# Half_Bridges.net
KiCad netlist of a schematic drawn in Altium Designer
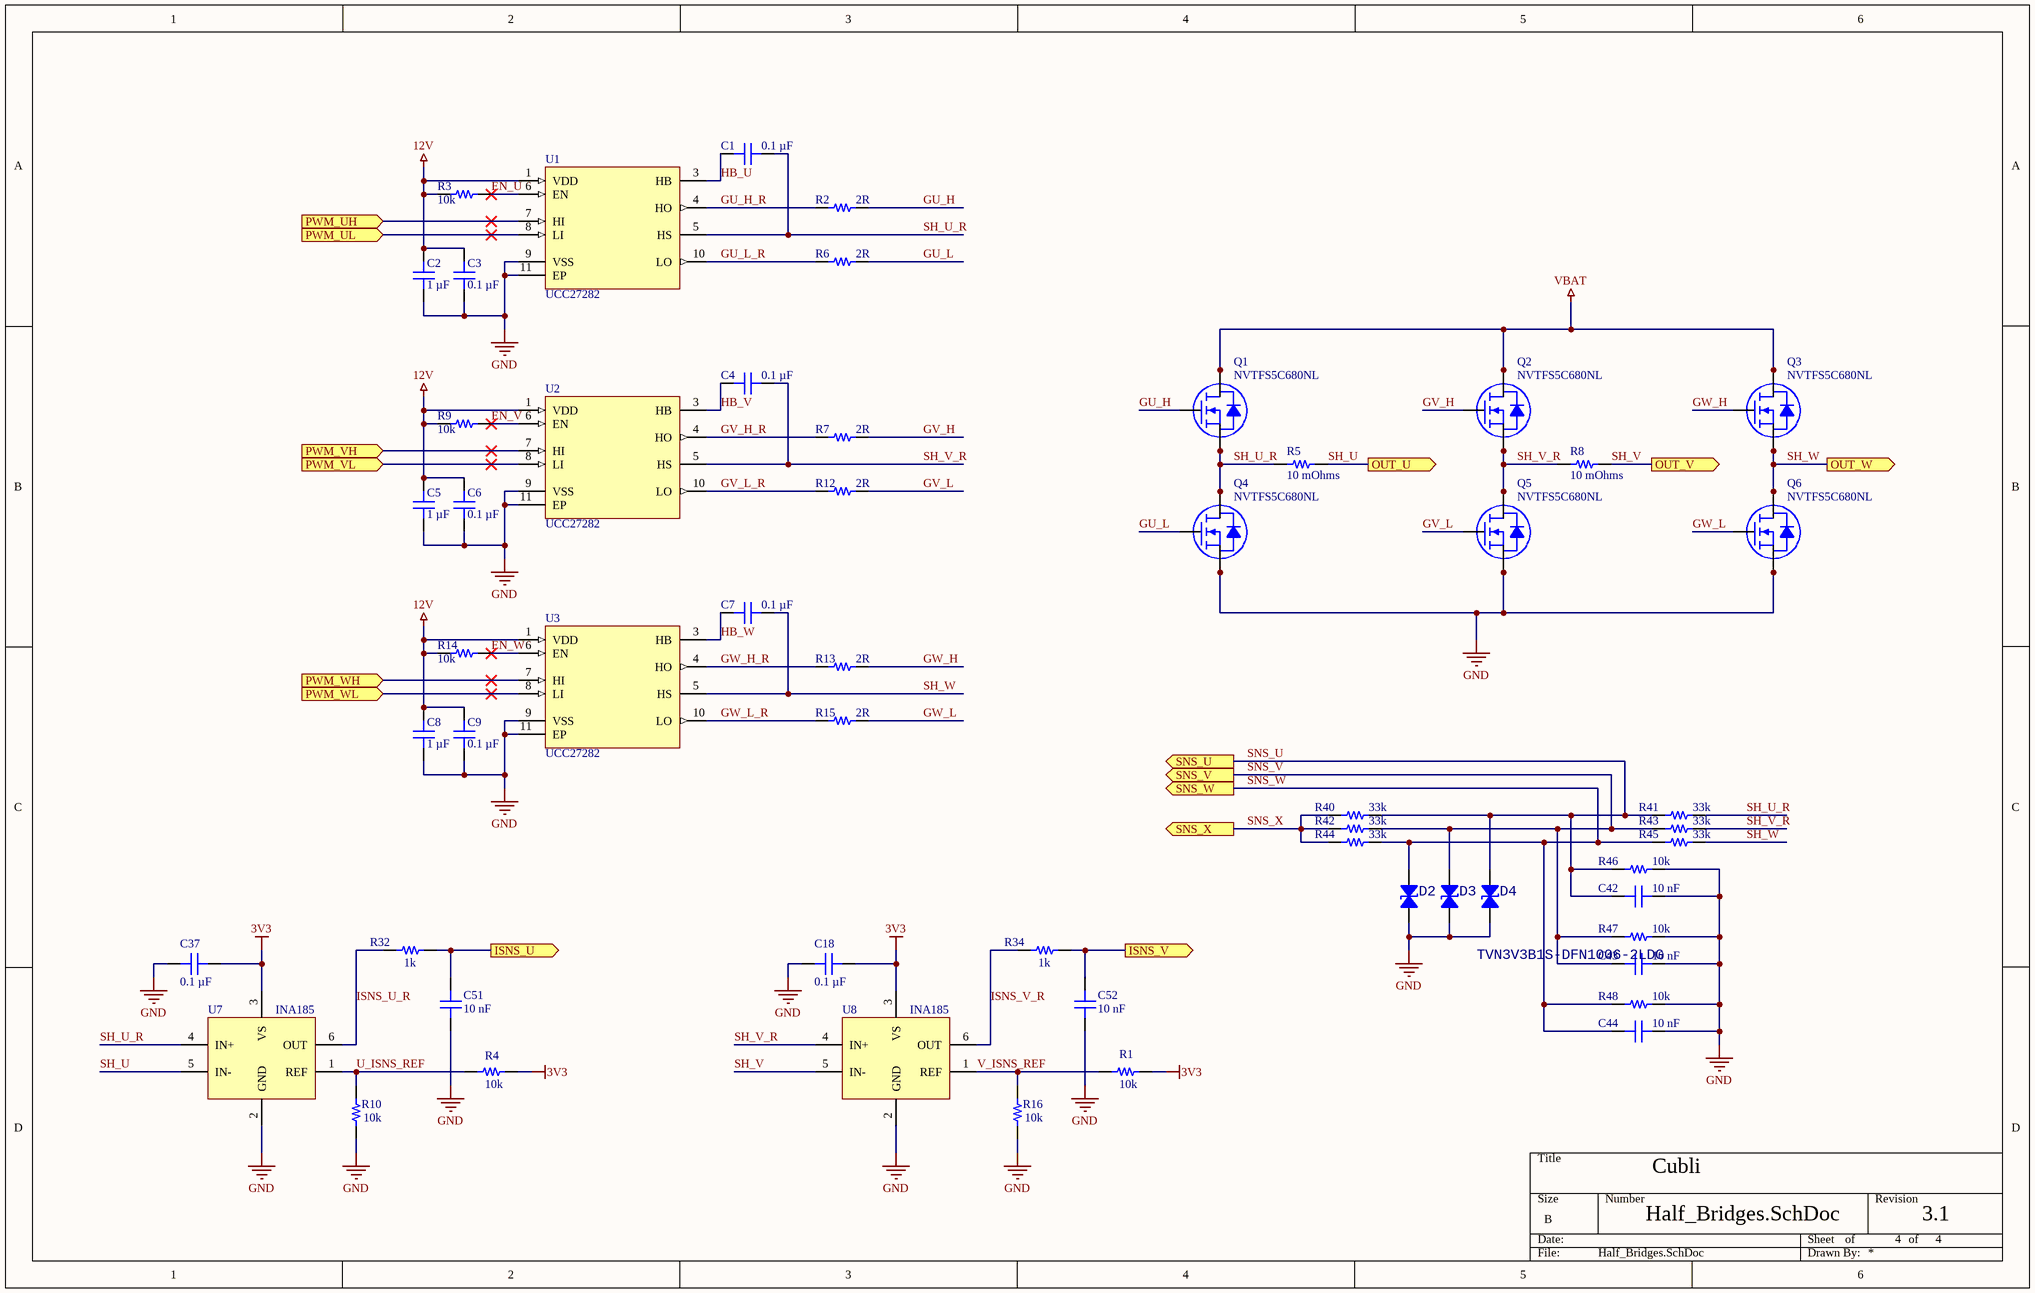
[diagram p0: Half_Bridges.SchDoc]

(export (version "E")
  (design (tool "Eeschema 10.0.6"))
  (components
    (comp (ref "C1")
      (value "0.1 µF")
      (footprint "CAP 0402_1005")
      (description "CAP CER 0.1UF 16V X7R 0402")
      (fields (field (name "PART NUMBER") "C0402C104K4RACAUTO") (field (name "MANUFACTURER") "KEMET"))
      (libsource (lib "Celestial Altium Library - altium_library") (part "Capacitor"))
    )
    (comp (ref "C2")
      (value "1 µF")
      (footprint "CAP 0402_1005")
      (description "CAP CER 0.1UF 16V X7R 0402")
      (fields (field (name "PART NUMBER") "C0402C104K4RACAUTO") (field (name "MANUFACTURER") "KEMET"))
      (libsource (lib "Celestial Altium Library - altium_library") (part "Capacitor"))
    )
    (comp (ref "C3")
      (value "0.1 µF")
      (footprint "CAP 0402_1005")
      (description "CAP CER 0.1UF 16V X7R 0402")
      (fields (field (name "PART NUMBER") "C0402C104K4RACAUTO") (field (name "MANUFACTURER") "KEMET"))
      (libsource (lib "Celestial Altium Library - altium_library") (part "Capacitor"))
    )
    (comp (ref "C4")
      (value "0.1 µF")
      (footprint "CAP 0402_1005")
      (description "CAP CER 0.1UF 16V X7R 0402")
      (fields (field (name "PART NUMBER") "C0402C104K4RACAUTO") (field (name "MANUFACTURER") "KEMET"))
      (libsource (lib "Celestial Altium Library - altium_library") (part "Capacitor"))
    )
    (comp (ref "C5")
      (value "1 µF")
      (footprint "CAP 0402_1005")
      (description "CAP CER 0.1UF 16V X7R 0402")
      (fields (field (name "PART NUMBER") "C0402C104K4RACAUTO") (field (name "MANUFACTURER") "KEMET"))
      (libsource (lib "Celestial Altium Library - altium_library") (part "Capacitor"))
    )
    (comp (ref "C6")
      (value "0.1 µF")
      (footprint "CAP 0402_1005")
      (description "CAP CER 0.1UF 16V X7R 0402")
      (fields (field (name "PART NUMBER") "C0402C104K4RACAUTO") (field (name "MANUFACTURER") "KEMET"))
      (libsource (lib "Celestial Altium Library - altium_library") (part "Capacitor"))
    )
    (comp (ref "C7")
      (value "0.1 µF")
      (footprint "CAP 0402_1005")
      (description "CAP CER 0.1UF 16V X7R 0402")
      (fields (field (name "PART NUMBER") "C0402C104K4RACAUTO") (field (name "MANUFACTURER") "KEMET"))
      (libsource (lib "Celestial Altium Library - altium_library") (part "Capacitor"))
    )
    (comp (ref "C8")
      (value "1 µF")
      (footprint "CAP 0402_1005")
      (description "CAP CER 0.1UF 16V X7R 0402")
      (fields (field (name "PART NUMBER") "C0402C104K4RACAUTO") (field (name "MANUFACTURER") "KEMET"))
      (libsource (lib "Celestial Altium Library - altium_library") (part "Capacitor"))
    )
    (comp (ref "C9")
      (value "0.1 µF")
      (footprint "CAP 0402_1005")
      (description "CAP CER 0.1UF 16V X7R 0402")
      (fields (field (name "PART NUMBER") "C0402C104K4RACAUTO") (field (name "MANUFACTURER") "KEMET"))
      (libsource (lib "Celestial Altium Library - altium_library") (part "Capacitor"))
    )
    (comp (ref "C18")
      (value "0.1 µF")
      (footprint "CAP 0402_1005")
      (description "CAP CER 0.1UF 16V X7R 0402")
      (fields (field (name "PART NUMBER") "C0402C104K4RACAUTO") (field (name "MANUFACTURER") "KEMET"))
      (libsource (lib "Celestial Altium Library - altium_library") (part "Capacitor"))
    )
    (comp (ref "C37")
      (value "0.1 µF")
      (footprint "CAP 0402_1005")
      (description "CAP CER 0.1UF 16V X7R 0402")
      (fields (field (name "PART NUMBER") "C0402C104K4RACAUTO") (field (name "MANUFACTURER") "KEMET"))
      (libsource (lib "Celestial Altium Library - altium_library") (part "Capacitor"))
    )
    (comp (ref "C42")
      (value "10 nF")
      (footprint "CAP 0402_1005")
      (description "CAP CER 0.1UF 16V X7R 0402")
      (fields (field (name "PART NUMBER") "C0402C104K4RACAUTO") (field (name "MANUFACTURER") "KEMET"))
      (libsource (lib "Celestial Altium Library - altium_library") (part "Capacitor"))
    )
    (comp (ref "C43")
      (value "10 nF")
      (footprint "CAP 0402_1005")
      (description "CAP CER 0.1UF 16V X7R 0402")
      (fields (field (name "PART NUMBER") "C0402C104K4RACAUTO") (field (name "MANUFACTURER") "KEMET"))
      (libsource (lib "Celestial Altium Library - altium_library") (part "Capacitor"))
    )
    (comp (ref "C44")
      (value "10 nF")
      (footprint "CAP 0402_1005")
      (description "CAP CER 0.1UF 16V X7R 0402")
      (fields (field (name "PART NUMBER") "C0402C104K4RACAUTO") (field (name "MANUFACTURER") "KEMET"))
      (libsource (lib "Celestial Altium Library - altium_library") (part "Capacitor"))
    )
    (comp (ref "C51")
      (value "10 nF")
      (footprint "CAP 0402_1005")
      (description "CAP CER 0.1UF 16V X7R 0402")
      (fields (field (name "PART NUMBER") "C0402C104K4RACAUTO") (field (name "MANUFACTURER") "KEMET"))
      (libsource (lib "Celestial Altium Library - altium_library") (part "Capacitor"))
    )
    (comp (ref "C52")
      (value "10 nF")
      (footprint "CAP 0402_1005")
      (description "CAP CER 0.1UF 16V X7R 0402")
      (fields (field (name "PART NUMBER") "C0402C104K4RACAUTO") (field (name "MANUFACTURER") "KEMET"))
      (libsource (lib "Celestial Altium Library - altium_library") (part "Capacitor"))
    )
    (comp (ref "D2")
      (value "TVN3V3B1S-DFN1006-2LDG")
      (footprint "0402")
      (description "TVS DIODE 3.3V 14.2PF DFN1006")
      (fields (field (name "MANUFACTURER") "INPAQ Technology Co., Ltd"))
      (libsource (lib "Celestial Altium Library - altium_library") (part "Diode TVS"))
    )
    (comp (ref "D3")
      (value "TVN3V3B1S-DFN1006-2LDG")
      (footprint "0402")
      (description "TVS DIODE 3.3V 14.2PF DFN1006")
      (fields (field (name "MANUFACTURER") "INPAQ Technology Co., Ltd"))
      (libsource (lib "Celestial Altium Library - altium_library") (part "Diode TVS"))
    )
    (comp (ref "D4")
      (value "TVN3V3B1S-DFN1006-2LDG")
      (footprint "0402")
      (description "TVS DIODE 3.3V 14.2PF DFN1006")
      (fields (field (name "MANUFACTURER") "INPAQ Technology Co., Ltd"))
      (libsource (lib "Celestial Altium Library - altium_library") (part "Diode TVS"))
    )
    (comp (ref "Q1")
      (value "NVTFS5C680NL")
      (footprint "NVTFS015N04CTAG")
      (description "N-FET")
      (libsource (lib "IC") (part "NVTFS5C680NL"))
    )
    (comp (ref "Q2")
      (value "NVTFS5C680NL")
      (footprint "NVTFS015N04CTAG")
      (description "N-FET")
      (libsource (lib "IC") (part "NVTFS5C680NL"))
    )
    (comp (ref "Q3")
      (value "NVTFS5C680NL")
      (footprint "NVTFS015N04CTAG")
      (description "N-FET")
      (libsource (lib "IC") (part "NVTFS5C680NL"))
    )
    (comp (ref "Q4")
      (value "NVTFS5C680NL")
      (footprint "NVTFS015N04CTAG")
      (description "N-FET")
      (libsource (lib "IC") (part "NVTFS5C680NL"))
    )
    (comp (ref "Q5")
      (value "NVTFS5C680NL")
      (footprint "NVTFS015N04CTAG")
      (description "N-FET")
      (libsource (lib "IC") (part "NVTFS5C680NL"))
    )
    (comp (ref "Q6")
      (value "NVTFS5C680NL")
      (footprint "NVTFS015N04CTAG")
      (description "N-FET")
      (libsource (lib "IC") (part "NVTFS5C680NL"))
    )
    (comp (ref "R1")
      (value "10k")
      (footprint "RES_0402")
      (description "RES 0402")
      (libsource (lib "IC") (part "RES_0402"))
    )
    (comp (ref "R2")
      (value "2R")
      (footprint "RES_0402")
      (description "RES 0402")
      (libsource (lib "IC") (part "RES_0402"))
    )
    (comp (ref "R3")
      (value "10k")
      (footprint "RES_0402")
      (description "RES 0402")
      (libsource (lib "IC") (part "RES_0402"))
    )
    (comp (ref "R4")
      (value "10k")
      (footprint "RES_0402")
      (description "RES 0402")
      (libsource (lib "IC") (part "RES_0402"))
    )
    (comp (ref "R5")
      (value "10 mOhms")
      (footprint "RES 1206_3216")
      (description "RES 0.039 OHM 1% 3/4W 1206")
      (fields (field (name "PART NUMBER") "KRL1632E-M-R039-F-T5") (field (name "MANUFACTURER") "Susumu"))
      (libsource (lib "Celestial Altium Library - altium_library") (part "Resistor"))
    )
    (comp (ref "R6")
      (value "2R")
      (footprint "RES_0402")
      (description "RES 0402")
      (libsource (lib "IC") (part "RES_0402"))
    )
    (comp (ref "R7")
      (value "2R")
      (footprint "RES_0402")
      (description "RES 0402")
      (libsource (lib "IC") (part "RES_0402"))
    )
    (comp (ref "R8")
      (value "10 mOhms")
      (footprint "RES 1206_3216")
      (description "RES 0.039 OHM 1% 3/4W 1206")
      (fields (field (name "PART NUMBER") "KRL1632E-M-R039-F-T5") (field (name "MANUFACTURER") "Susumu"))
      (libsource (lib "Celestial Altium Library - altium_library") (part "Resistor"))
    )
    (comp (ref "R9")
      (value "10k")
      (footprint "RES_0402")
      (description "RES 0402")
      (libsource (lib "IC") (part "RES_0402"))
    )
    (comp (ref "R10")
      (value "10k")
      (footprint "RES_0402")
      (description "RES 0402")
      (libsource (lib "IC") (part "RES_0402"))
    )
    (comp (ref "R12")
      (value "2R")
      (footprint "RES_0402")
      (description "RES 0402")
      (libsource (lib "IC") (part "RES_0402"))
    )
    (comp (ref "R13")
      (value "2R")
      (footprint "RES_0402")
      (description "RES 0402")
      (libsource (lib "IC") (part "RES_0402"))
    )
    (comp (ref "R14")
      (value "10k")
      (footprint "RES_0402")
      (description "RES 0402")
      (libsource (lib "IC") (part "RES_0402"))
    )
    (comp (ref "R15")
      (value "2R")
      (footprint "RES_0402")
      (description "RES 0402")
      (libsource (lib "IC") (part "RES_0402"))
    )
    (comp (ref "R16")
      (value "10k")
      (footprint "RES_0402")
      (description "RES 0402")
      (libsource (lib "IC") (part "RES_0402"))
    )
    (comp (ref "R32")
      (value "1k")
      (footprint "RES_0402")
      (description "RES 0402")
      (libsource (lib "IC") (part "RES_0402"))
    )
    (comp (ref "R34")
      (value "1k")
      (footprint "RES_0402")
      (description "RES 0402")
      (libsource (lib "IC") (part "RES_0402"))
    )
    (comp (ref "R40")
      (value "33k")
      (footprint "RES_0402")
      (description "RES 0402")
      (libsource (lib "IC") (part "RES_0402"))
    )
    (comp (ref "R41")
      (value "33k")
      (footprint "RES_0402")
      (description "RES 0402")
      (libsource (lib "IC") (part "RES_0402"))
    )
    (comp (ref "R42")
      (value "33k")
      (footprint "RES_0402")
      (description "RES 0402")
      (libsource (lib "IC") (part "RES_0402"))
    )
    (comp (ref "R43")
      (value "33k")
      (footprint "RES_0402")
      (description "RES 0402")
      (libsource (lib "IC") (part "RES_0402"))
    )
    (comp (ref "R44")
      (value "33k")
      (footprint "RES_0402")
      (description "RES 0402")
      (libsource (lib "IC") (part "RES_0402"))
    )
    (comp (ref "R45")
      (value "33k")
      (footprint "RES_0402")
      (description "RES 0402")
      (libsource (lib "IC") (part "RES_0402"))
    )
    (comp (ref "R46")
      (value "10k")
      (footprint "RES_0402")
      (description "RES 0402")
      (libsource (lib "IC") (part "RES_0402"))
    )
    (comp (ref "R47")
      (value "10k")
      (footprint "RES_0402")
      (description "RES 0402")
      (libsource (lib "IC") (part "RES_0402"))
    )
    (comp (ref "R48")
      (value "10k")
      (footprint "RES_0402")
      (description "RES 0402")
      (libsource (lib "IC") (part "RES_0402"))
    )
    (comp (ref "U1")
      (value "UCC27282")
      (footprint "VSON-10")
      (description "3-A, 120-V half bridge gate driver with 5-V UVLO, interlock and enable 10-VSON -40 to 125")
      (fields (field (name "MF") "Texas Instruments") (field (name "MP") "UCC27282DRCR"))
      (libsource (lib "IC") (part "UCC27282DRCR"))
    )
    (comp (ref "U2")
      (value "UCC27282")
      (footprint "VSON-10")
      (description "3-A, 120-V half bridge gate driver with 5-V UVLO, interlock and enable 10-VSON -40 to 125")
      (fields (field (name "MF") "Texas Instruments") (field (name "MP") "UCC27282DRCR"))
      (libsource (lib "IC") (part "UCC27282DRCR"))
    )
    (comp (ref "U3")
      (value "UCC27282")
      (footprint "VSON-10")
      (description "3-A, 120-V half bridge gate driver with 5-V UVLO, interlock and enable 10-VSON -40 to 125")
      (fields (field (name "MF") "Texas Instruments") (field (name "MP") "UCC27282DRCR"))
      (libsource (lib "IC") (part "UCC27282DRCR"))
    )
    (comp (ref "U7")
      (value "INA185")
      (footprint "TI SC70-6 DCK")
      (description "INA185A2")
      (libsource (lib "IC") (part "INA185"))
    )
    (comp (ref "U8")
      (value "INA185")
      (footprint "TI SC70-6 DCK")
      (description "INA185A2")
      (libsource (lib "IC") (part "INA185"))
    )
  )
  (nets
    (net (code "1") (name "/EN_U") (class "Default")
      (node (ref "R3") (pin "2") (pinfunction "2_2") (pintype "passive"))
      (node (ref "U1") (pin "6") (pinfunction "EN_6") (pintype "input"))
    )
    (net (code "2") (name "/EN_V") (class "Default")
      (node (ref "R9") (pin "2") (pinfunction "2_2") (pintype "passive"))
      (node (ref "U2") (pin "6") (pinfunction "EN_6") (pintype "input"))
    )
    (net (code "3") (name "/EN_W") (class "Default")
      (node (ref "R14") (pin "2") (pinfunction "2_2") (pintype "passive"))
      (node (ref "U3") (pin "6") (pinfunction "EN_6") (pintype "input"))
    )
    (net (code "4") (name "/GU_H") (class "Default")
      (node (ref "Q1") (pin "4") (pinfunction "G_4") (pintype "passive"))
      (node (ref "R2") (pin "2") (pinfunction "2_2") (pintype "passive"))
    )
    (net (code "5") (name "/GU_H_R") (class "Default")
      (node (ref "R2") (pin "1") (pinfunction "1_1") (pintype "passive"))
      (node (ref "U1") (pin "4") (pinfunction "HO_4") (pintype "output"))
    )
    (net (code "6") (name "/GU_L") (class "Default")
      (node (ref "Q4") (pin "4") (pinfunction "G_4") (pintype "passive"))
      (node (ref "R6") (pin "2") (pinfunction "2_2") (pintype "passive"))
    )
    (net (code "7") (name "/GU_L_R") (class "Default")
      (node (ref "R6") (pin "1") (pinfunction "1_1") (pintype "passive"))
      (node (ref "U1") (pin "10") (pinfunction "LO_10") (pintype "output"))
    )
    (net (code "8") (name "/GV_H") (class "Default")
      (node (ref "Q2") (pin "4") (pinfunction "G_4") (pintype "passive"))
      (node (ref "R7") (pin "2") (pinfunction "2_2") (pintype "passive"))
    )
    (net (code "9") (name "/GV_H_R") (class "Default")
      (node (ref "R7") (pin "1") (pinfunction "1_1") (pintype "passive"))
      (node (ref "U2") (pin "4") (pinfunction "HO_4") (pintype "output"))
    )
    (net (code "10") (name "/GV_L") (class "Default")
      (node (ref "Q5") (pin "4") (pinfunction "G_4") (pintype "passive"))
      (node (ref "R12") (pin "2") (pinfunction "2_2") (pintype "passive"))
    )
    (net (code "11") (name "/GV_L_R") (class "Default")
      (node (ref "R12") (pin "1") (pinfunction "1_1") (pintype "passive"))
      (node (ref "U2") (pin "10") (pinfunction "LO_10") (pintype "output"))
    )
    (net (code "12") (name "/GW_H") (class "Default")
      (node (ref "Q3") (pin "4") (pinfunction "G_4") (pintype "passive"))
      (node (ref "R13") (pin "2") (pinfunction "2_2") (pintype "passive"))
    )
    (net (code "13") (name "/GW_H_R") (class "Default")
      (node (ref "R13") (pin "1") (pinfunction "1_1") (pintype "passive"))
      (node (ref "U3") (pin "4") (pinfunction "HO_4") (pintype "output"))
    )
    (net (code "14") (name "/GW_L") (class "Default")
      (node (ref "Q6") (pin "4") (pinfunction "G_4") (pintype "passive"))
      (node (ref "R15") (pin "2") (pinfunction "2_2") (pintype "passive"))
    )
    (net (code "15") (name "/GW_L_R") (class "Default")
      (node (ref "R15") (pin "1") (pinfunction "1_1") (pintype "passive"))
      (node (ref "U3") (pin "10") (pinfunction "LO_10") (pintype "output"))
    )
    (net (code "16") (name "/HB_U") (class "Default")
      (node (ref "C1") (pin "2") (pinfunction "2_2") (pintype "passive"))
      (node (ref "U1") (pin "3") (pinfunction "HB_3") (pintype "power_in"))
    )
    (net (code "17") (name "/HB_V") (class "Default")
      (node (ref "C4") (pin "2") (pinfunction "2_2") (pintype "passive"))
      (node (ref "U2") (pin "3") (pinfunction "HB_3") (pintype "power_in"))
    )
    (net (code "18") (name "/HB_W") (class "Default")
      (node (ref "C7") (pin "2") (pinfunction "2_2") (pintype "passive"))
      (node (ref "U3") (pin "3") (pinfunction "HB_3") (pintype "power_in"))
    )
    (net (code "19") (name "/ISNS_U") (class "Default")
      (node (ref "C51") (pin "1") (pinfunction "1_1") (pintype "passive"))
      (node (ref "R32") (pin "1") (pinfunction "1_1") (pintype "passive"))
    )
    (net (code "20") (name "/ISNS_U_R") (class "Default")
      (node (ref "R32") (pin "2") (pinfunction "2_2") (pintype "passive"))
      (node (ref "U7") (pin "6") (pinfunction "OUT_6") (pintype "passive"))
    )
    (net (code "21") (name "/ISNS_V") (class "Default")
      (node (ref "C52") (pin "1") (pinfunction "1_1") (pintype "passive"))
      (node (ref "R34") (pin "1") (pinfunction "1_1") (pintype "passive"))
    )
    (net (code "22") (name "/ISNS_V_R") (class "Default")
      (node (ref "R34") (pin "2") (pinfunction "2_2") (pintype "passive"))
      (node (ref "U8") (pin "6") (pinfunction "OUT_6") (pintype "passive"))
    )
    (net (code "23") (name "/PWM_UH") (class "Default")
      (node (ref "U1") (pin "7") (pinfunction "HI_7") (pintype "input"))
    )
    (net (code "24") (name "/PWM_UL") (class "Default")
      (node (ref "U1") (pin "8") (pinfunction "LI_8") (pintype "input"))
    )
    (net (code "25") (name "/PWM_VH") (class "Default")
      (node (ref "U2") (pin "7") (pinfunction "HI_7") (pintype "input"))
    )
    (net (code "26") (name "/PWM_VL") (class "Default")
      (node (ref "U2") (pin "8") (pinfunction "LI_8") (pintype "input"))
    )
    (net (code "27") (name "/PWM_WH") (class "Default")
      (node (ref "U3") (pin "7") (pinfunction "HI_7") (pintype "input"))
    )
    (net (code "28") (name "/PWM_WL") (class "Default")
      (node (ref "U3") (pin "8") (pinfunction "LI_8") (pintype "input"))
    )
    (net (code "29") (name "/SH_U") (class "Default")
      (node (ref "R5") (pin "2") (pinfunction "2_2") (pintype "passive"))
      (node (ref "U7") (pin "5") (pinfunction "IN-_5") (pintype "passive"))
    )
    (net (code "30") (name "/SH_U_R") (class "Default")
      (node (ref "C1") (pin "1") (pinfunction "1_1") (pintype "passive"))
      (node (ref "Q1") (pin "1") (pinfunction "S_1") (pintype "passive"))
      (node (ref "Q1") (pin "2") (pinfunction "S_2") (pintype "passive"))
      (node (ref "Q1") (pin "3") (pinfunction "S_3") (pintype "passive"))
      (node (ref "Q4") (pin "5") (pinfunction "D_5") (pintype "passive"))
      (node (ref "Q4") (pin "6") (pinfunction "D_6") (pintype "passive"))
      (node (ref "Q4") (pin "7") (pinfunction "D_7") (pintype "passive"))
      (node (ref "Q4") (pin "8") (pinfunction "D_8") (pintype "passive"))
      (node (ref "R41") (pin "1") (pinfunction "1_1") (pintype "passive"))
      (node (ref "R5") (pin "1") (pinfunction "1_1") (pintype "passive"))
      (node (ref "U1") (pin "5") (pinfunction "HS_5") (pintype "power_in"))
      (node (ref "U7") (pin "4") (pinfunction "IN+_4") (pintype "passive"))
    )
    (net (code "31") (name "/SH_V") (class "Default")
      (node (ref "R8") (pin "2") (pinfunction "2_2") (pintype "passive"))
      (node (ref "U8") (pin "5") (pinfunction "IN-_5") (pintype "passive"))
    )
    (net (code "32") (name "/SH_V_R") (class "Default")
      (node (ref "C4") (pin "1") (pinfunction "1_1") (pintype "passive"))
      (node (ref "Q2") (pin "1") (pinfunction "S_1") (pintype "passive"))
      (node (ref "Q2") (pin "2") (pinfunction "S_2") (pintype "passive"))
      (node (ref "Q2") (pin "3") (pinfunction "S_3") (pintype "passive"))
      (node (ref "Q5") (pin "5") (pinfunction "D_5") (pintype "passive"))
      (node (ref "Q5") (pin "6") (pinfunction "D_6") (pintype "passive"))
      (node (ref "Q5") (pin "7") (pinfunction "D_7") (pintype "passive"))
      (node (ref "Q5") (pin "8") (pinfunction "D_8") (pintype "passive"))
      (node (ref "R43") (pin "1") (pinfunction "1_1") (pintype "passive"))
      (node (ref "R8") (pin "1") (pinfunction "1_1") (pintype "passive"))
      (node (ref "U2") (pin "5") (pinfunction "HS_5") (pintype "power_in"))
      (node (ref "U8") (pin "4") (pinfunction "IN+_4") (pintype "passive"))
    )
    (net (code "33") (name "/SH_W") (class "Default")
      (node (ref "C7") (pin "1") (pinfunction "1_1") (pintype "passive"))
      (node (ref "Q3") (pin "1") (pinfunction "S_1") (pintype "passive"))
      (node (ref "Q3") (pin "2") (pinfunction "S_2") (pintype "passive"))
      (node (ref "Q3") (pin "3") (pinfunction "S_3") (pintype "passive"))
      (node (ref "Q6") (pin "5") (pinfunction "D_5") (pintype "passive"))
      (node (ref "Q6") (pin "6") (pinfunction "D_6") (pintype "passive"))
      (node (ref "Q6") (pin "7") (pinfunction "D_7") (pintype "passive"))
      (node (ref "Q6") (pin "8") (pinfunction "D_8") (pintype "passive"))
      (node (ref "R45") (pin "1") (pinfunction "1_1") (pintype "passive"))
      (node (ref "U3") (pin "5") (pinfunction "HS_5") (pintype "power_in"))
    )
    (net (code "34") (name "/SNS_U") (class "Default")
      (node (ref "C42") (pin "2") (pinfunction "2_2") (pintype "passive"))
      (node (ref "D4") (pin "2") (pinfunction "2_2") (pintype "passive"))
      (node (ref "R40") (pin "1") (pinfunction "1_1") (pintype "passive"))
      (node (ref "R41") (pin "2") (pinfunction "2_2") (pintype "passive"))
      (node (ref "R46") (pin "1") (pinfunction "1_1") (pintype "passive"))
    )
    (net (code "35") (name "/SNS_V") (class "Default")
      (node (ref "C43") (pin "2") (pinfunction "2_2") (pintype "passive"))
      (node (ref "D3") (pin "2") (pinfunction "2_2") (pintype "passive"))
      (node (ref "R42") (pin "1") (pinfunction "1_1") (pintype "passive"))
      (node (ref "R43") (pin "2") (pinfunction "2_2") (pintype "passive"))
      (node (ref "R47") (pin "1") (pinfunction "1_1") (pintype "passive"))
    )
    (net (code "36") (name "/SNS_W") (class "Default")
      (node (ref "C44") (pin "2") (pinfunction "2_2") (pintype "passive"))
      (node (ref "D2") (pin "2") (pinfunction "2_2") (pintype "passive"))
      (node (ref "R44") (pin "1") (pinfunction "1_1") (pintype "passive"))
      (node (ref "R45") (pin "2") (pinfunction "2_2") (pintype "passive"))
      (node (ref "R48") (pin "1") (pinfunction "1_1") (pintype "passive"))
    )
    (net (code "37") (name "/SNS_X") (class "Default")
      (node (ref "R40") (pin "2") (pinfunction "2_2") (pintype "passive"))
      (node (ref "R42") (pin "2") (pinfunction "2_2") (pintype "passive"))
      (node (ref "R44") (pin "2") (pinfunction "2_2") (pintype "passive"))
    )
    (net (code "38") (name "/U_ISNS_REF") (class "Default")
      (node (ref "R10") (pin "1") (pinfunction "1_1") (pintype "passive"))
      (node (ref "R4") (pin "2") (pinfunction "2_2") (pintype "passive"))
      (node (ref "U7") (pin "1") (pinfunction "REF_1") (pintype "passive"))
    )
    (net (code "39") (name "/V_ISNS_REF") (class "Default")
      (node (ref "R1") (pin "2") (pinfunction "2_2") (pintype "passive"))
      (node (ref "R16") (pin "1") (pinfunction "1_1") (pintype "passive"))
      (node (ref "U8") (pin "1") (pinfunction "REF_1") (pintype "passive"))
    )
    (net (code "40") (name "3V3") (class "Default")
      (node (ref "C18") (pin "1") (pinfunction "1_1") (pintype "passive"))
      (node (ref "C37") (pin "1") (pinfunction "1_1") (pintype "passive"))
      (node (ref "R1") (pin "1") (pinfunction "1_1") (pintype "passive"))
      (node (ref "R4") (pin "1") (pinfunction "1_1") (pintype "passive"))
      (node (ref "U7") (pin "3") (pinfunction "VS_3") (pintype "passive"))
      (node (ref "U8") (pin "3") (pinfunction "VS_3") (pintype "passive"))
    )
    (net (code "41") (name "12V") (class "Default")
      (node (ref "C2") (pin "1") (pinfunction "1_1") (pintype "passive"))
      (node (ref "C3") (pin "1") (pinfunction "1_1") (pintype "passive"))
      (node (ref "C5") (pin "1") (pinfunction "1_1") (pintype "passive"))
      (node (ref "C6") (pin "1") (pinfunction "1_1") (pintype "passive"))
      (node (ref "C8") (pin "1") (pinfunction "1_1") (pintype "passive"))
      (node (ref "C9") (pin "1") (pinfunction "1_1") (pintype "passive"))
      (node (ref "R14") (pin "1") (pinfunction "1_1") (pintype "passive"))
      (node (ref "R3") (pin "1") (pinfunction "1_1") (pintype "passive"))
      (node (ref "R9") (pin "1") (pinfunction "1_1") (pintype "passive"))
      (node (ref "U1") (pin "1") (pinfunction "VDD_1") (pintype "input"))
      (node (ref "U2") (pin "1") (pinfunction "VDD_1") (pintype "input"))
      (node (ref "U3") (pin "1") (pinfunction "VDD_1") (pintype "input"))
    )
    (net (code "42") (name "GND") (class "Default")
      (node (ref "C18") (pin "2") (pinfunction "2_2") (pintype "passive"))
      (node (ref "C2") (pin "2") (pinfunction "2_2") (pintype "passive"))
      (node (ref "C3") (pin "2") (pinfunction "2_2") (pintype "passive"))
      (node (ref "C37") (pin "2") (pinfunction "2_2") (pintype "passive"))
      (node (ref "C42") (pin "1") (pinfunction "1_1") (pintype "passive"))
      (node (ref "C43") (pin "1") (pinfunction "1_1") (pintype "passive"))
      (node (ref "C44") (pin "1") (pinfunction "1_1") (pintype "passive"))
      (node (ref "C5") (pin "2") (pinfunction "2_2") (pintype "passive"))
      (node (ref "C51") (pin "2") (pinfunction "2_2") (pintype "passive"))
      (node (ref "C52") (pin "2") (pinfunction "2_2") (pintype "passive"))
      (node (ref "C6") (pin "2") (pinfunction "2_2") (pintype "passive"))
      (node (ref "C8") (pin "2") (pinfunction "2_2") (pintype "passive"))
      (node (ref "C9") (pin "2") (pinfunction "2_2") (pintype "passive"))
      (node (ref "D2") (pin "1") (pinfunction "1_1") (pintype "passive"))
      (node (ref "D3") (pin "1") (pinfunction "1_1") (pintype "passive"))
      (node (ref "D4") (pin "1") (pinfunction "1_1") (pintype "passive"))
      (node (ref "Q4") (pin "1") (pinfunction "S_1") (pintype "passive"))
      (node (ref "Q4") (pin "2") (pinfunction "S_2") (pintype "passive"))
      (node (ref "Q4") (pin "3") (pinfunction "S_3") (pintype "passive"))
      (node (ref "Q5") (pin "1") (pinfunction "S_1") (pintype "passive"))
      (node (ref "Q5") (pin "2") (pinfunction "S_2") (pintype "passive"))
      (node (ref "Q5") (pin "3") (pinfunction "S_3") (pintype "passive"))
      (node (ref "Q6") (pin "1") (pinfunction "S_1") (pintype "passive"))
      (node (ref "Q6") (pin "2") (pinfunction "S_2") (pintype "passive"))
      (node (ref "Q6") (pin "3") (pinfunction "S_3") (pintype "passive"))
      (node (ref "R10") (pin "2") (pinfunction "2_2") (pintype "passive"))
      (node (ref "R16") (pin "2") (pinfunction "2_2") (pintype "passive"))
      (node (ref "R46") (pin "2") (pinfunction "2_2") (pintype "passive"))
      (node (ref "R47") (pin "2") (pinfunction "2_2") (pintype "passive"))
      (node (ref "R48") (pin "2") (pinfunction "2_2") (pintype "passive"))
      (node (ref "U1") (pin "11") (pinfunction "EP_11") (pintype "passive"))
      (node (ref "U1") (pin "9") (pinfunction "VSS_9") (pintype "power_in"))
      (node (ref "U2") (pin "11") (pinfunction "EP_11") (pintype "passive"))
      (node (ref "U2") (pin "9") (pinfunction "VSS_9") (pintype "power_in"))
      (node (ref "U3") (pin "11") (pinfunction "EP_11") (pintype "passive"))
      (node (ref "U3") (pin "9") (pinfunction "VSS_9") (pintype "power_in"))
      (node (ref "U7") (pin "2") (pinfunction "GND_2") (pintype "passive"))
      (node (ref "U8") (pin "2") (pinfunction "GND_2") (pintype "passive"))
    )
    (net (code "43") (name "VBAT") (class "Default")
      (node (ref "Q1") (pin "5") (pinfunction "D_5") (pintype "passive"))
      (node (ref "Q1") (pin "6") (pinfunction "D_6") (pintype "passive"))
      (node (ref "Q1") (pin "7") (pinfunction "D_7") (pintype "passive"))
      (node (ref "Q1") (pin "8") (pinfunction "D_8") (pintype "passive"))
      (node (ref "Q2") (pin "5") (pinfunction "D_5") (pintype "passive"))
      (node (ref "Q2") (pin "6") (pinfunction "D_6") (pintype "passive"))
      (node (ref "Q2") (pin "7") (pinfunction "D_7") (pintype "passive"))
      (node (ref "Q2") (pin "8") (pinfunction "D_8") (pintype "passive"))
      (node (ref "Q3") (pin "5") (pinfunction "D_5") (pintype "passive"))
      (node (ref "Q3") (pin "6") (pinfunction "D_6") (pintype "passive"))
      (node (ref "Q3") (pin "7") (pinfunction "D_7") (pintype "passive"))
      (node (ref "Q3") (pin "8") (pinfunction "D_8") (pintype "passive"))
    )
  )
)
